# DACs.net
KiCad netlist of a schematic drawn in Altium Designer
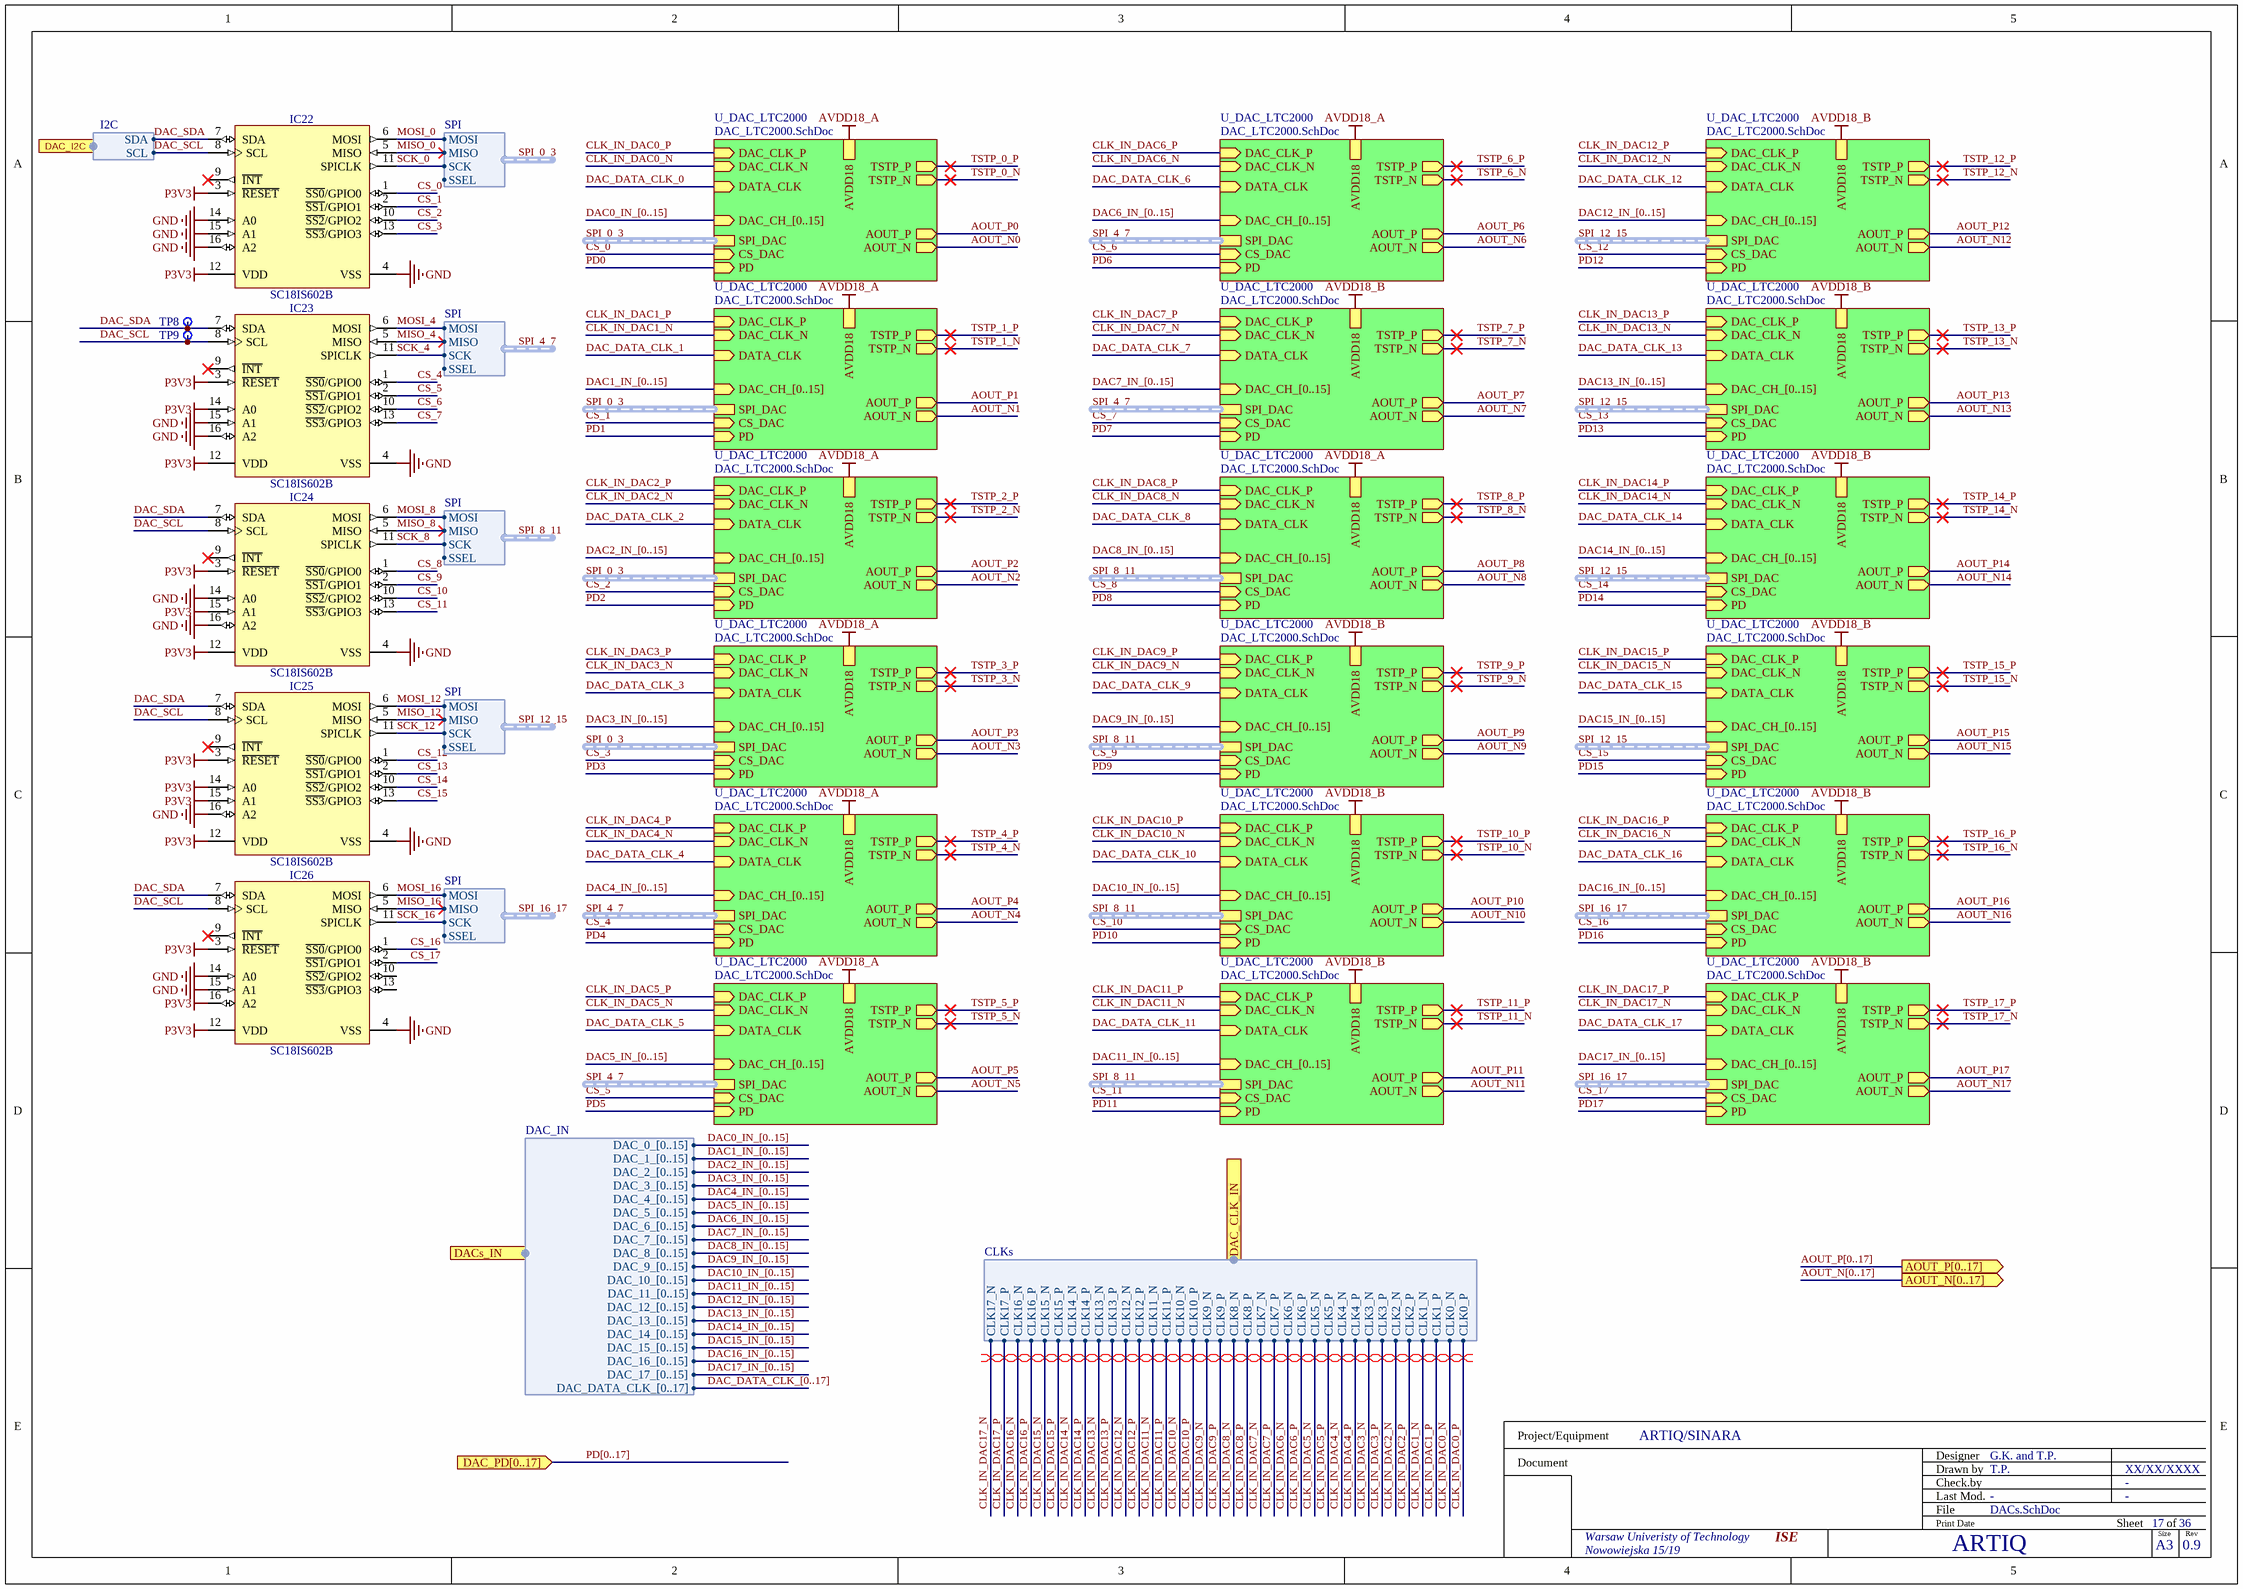
[diagram p0: DACs.SchDoc]

(export (version "E")
  (design (tool "Eeschema 10.0.6"))
  (components
    (comp (ref "IC22")
      (value "SC18IS602B")
      (footprint "SOP65P640X110-16N")
      (description "I2C-bus to SPI bridge")
      (fields (field (name "MANUFACTURER") "NXP SEMICONDUCTORS") (field (name "AUTHOR") "CERN DEM MR"))
      (libsource (lib "ICs And Semiconductors") (part "SC18IS602B"))
    )
    (comp (ref "IC23")
      (value "SC18IS602B")
      (footprint "SOP65P640X110-16N")
      (description "I2C-bus to SPI bridge")
      (fields (field (name "MANUFACTURER") "NXP SEMICONDUCTORS") (field (name "AUTHOR") "CERN DEM MR"))
      (libsource (lib "ICs And Semiconductors") (part "SC18IS602B"))
    )
    (comp (ref "IC24")
      (value "SC18IS602B")
      (footprint "SOP65P640X110-16N")
      (description "I2C-bus to SPI bridge")
      (fields (field (name "MANUFACTURER") "NXP SEMICONDUCTORS") (field (name "AUTHOR") "CERN DEM MR"))
      (libsource (lib "ICs And Semiconductors") (part "SC18IS602B"))
    )
    (comp (ref "IC25")
      (value "SC18IS602B")
      (footprint "SOP65P640X110-16N")
      (description "I2C-bus to SPI bridge")
      (fields (field (name "MANUFACTURER") "NXP SEMICONDUCTORS") (field (name "AUTHOR") "CERN DEM MR"))
      (libsource (lib "ICs And Semiconductors") (part "SC18IS602B"))
    )
    (comp (ref "IC26")
      (value "SC18IS602B")
      (footprint "SOP65P640X110-16N")
      (description "I2C-bus to SPI bridge")
      (fields (field (name "MANUFACTURER") "NXP SEMICONDUCTORS") (field (name "AUTHOR") "CERN DEM MR"))
      (libsource (lib "ICs And Semiconductors") (part "SC18IS602B"))
    )
    (comp (ref "TP8")
      (value "Test Point")
      (footprint "TPS127")
      (fields (field (name "PART NUMBER") "SMD_PAD_1.27X1.27MM") (field (name "AUTHOR") "CERN DEM JLC"))
      (libsource (lib "Eletro-mechanical") (part "Test Point"))
    )
    (comp (ref "TP9")
      (value "Test Point")
      (footprint "TPS127")
      (fields (field (name "PART NUMBER") "SMD_PAD_1.27X1.27MM") (field (name "AUTHOR") "CERN DEM JLC"))
      (libsource (lib "Eletro-mechanical") (part "Test Point"))
    )
  )
  (nets
    (net (code "376") (name "/CS_0") (class "Default")
      (node (ref "IC22") (pin "1") (pinfunction "~{SS0}/GPIO0_1") (pintype "bidirectional"))
    )
    (net (code "377") (name "/CS_1") (class "Default")
      (node (ref "IC22") (pin "2") (pinfunction "~{SS1}/GPIO1_2") (pintype "bidirectional"))
    )
    (net (code "378") (name "/CS_2") (class "Default")
      (node (ref "IC22") (pin "10") (pinfunction "~{SS2}/GPIO2_10") (pintype "bidirectional"))
    )
    (net (code "379") (name "/CS_3") (class "Default")
      (node (ref "IC22") (pin "13") (pinfunction "~{SS3}/GPIO3_13") (pintype "bidirectional"))
    )
    (net (code "380") (name "/CS_4") (class "Default")
      (node (ref "IC23") (pin "1") (pinfunction "~{SS0}/GPIO0_1") (pintype "bidirectional"))
    )
    (net (code "381") (name "/CS_5") (class "Default")
      (node (ref "IC23") (pin "2") (pinfunction "~{SS1}/GPIO1_2") (pintype "bidirectional"))
    )
    (net (code "382") (name "/CS_6") (class "Default")
      (node (ref "IC23") (pin "10") (pinfunction "~{SS2}/GPIO2_10") (pintype "bidirectional"))
    )
    (net (code "383") (name "/CS_7") (class "Default")
      (node (ref "IC23") (pin "13") (pinfunction "~{SS3}/GPIO3_13") (pintype "bidirectional"))
    )
    (net (code "384") (name "/CS_8") (class "Default")
      (node (ref "IC24") (pin "1") (pinfunction "~{SS0}/GPIO0_1") (pintype "bidirectional"))
    )
    (net (code "385") (name "/CS_9") (class "Default")
      (node (ref "IC24") (pin "2") (pinfunction "~{SS1}/GPIO1_2") (pintype "bidirectional"))
    )
    (net (code "386") (name "/CS_10") (class "Default")
      (node (ref "IC24") (pin "10") (pinfunction "~{SS2}/GPIO2_10") (pintype "bidirectional"))
    )
    (net (code "387") (name "/CS_11") (class "Default")
      (node (ref "IC24") (pin "13") (pinfunction "~{SS3}/GPIO3_13") (pintype "bidirectional"))
    )
    (net (code "388") (name "/CS_12") (class "Default")
      (node (ref "IC25") (pin "1") (pinfunction "~{SS0}/GPIO0_1") (pintype "bidirectional"))
    )
    (net (code "389") (name "/CS_13") (class "Default")
      (node (ref "IC25") (pin "2") (pinfunction "~{SS1}/GPIO1_2") (pintype "bidirectional"))
    )
    (net (code "390") (name "/CS_14") (class "Default")
      (node (ref "IC25") (pin "10") (pinfunction "~{SS2}/GPIO2_10") (pintype "bidirectional"))
    )
    (net (code "391") (name "/CS_15") (class "Default")
      (node (ref "IC25") (pin "13") (pinfunction "~{SS3}/GPIO3_13") (pintype "bidirectional"))
    )
    (net (code "392") (name "/CS_16") (class "Default")
      (node (ref "IC26") (pin "1") (pinfunction "~{SS0}/GPIO0_1") (pintype "bidirectional"))
    )
    (net (code "393") (name "/CS_17") (class "Default")
      (node (ref "IC26") (pin "2") (pinfunction "~{SS1}/GPIO1_2") (pintype "bidirectional"))
    )
    (net (code "430") (name "/DAC_SCL") (class "Default")
      (node (ref "IC22") (pin "8") (pinfunction "SCL_8") (pintype "input"))
      (node (ref "IC23") (pin "8") (pinfunction "SCL_8") (pintype "input"))
      (node (ref "IC24") (pin "8") (pinfunction "SCL_8") (pintype "input"))
      (node (ref "IC25") (pin "8") (pinfunction "SCL_8") (pintype "input"))
      (node (ref "IC26") (pin "8") (pinfunction "SCL_8") (pintype "input"))
      (node (ref "TP9") (pin "1") (pinfunction "1_1") (pintype "bidirectional"))
    )
    (net (code "431") (name "/DAC_SDA") (class "Default")
      (node (ref "IC22") (pin "7") (pinfunction "SDA_7") (pintype "bidirectional"))
      (node (ref "IC23") (pin "7") (pinfunction "SDA_7") (pintype "bidirectional"))
      (node (ref "IC24") (pin "7") (pinfunction "SDA_7") (pintype "bidirectional"))
      (node (ref "IC25") (pin "7") (pinfunction "SDA_7") (pintype "bidirectional"))
      (node (ref "IC26") (pin "7") (pinfunction "SDA_7") (pintype "bidirectional"))
      (node (ref "TP8") (pin "1") (pinfunction "1_1") (pintype "bidirectional"))
    )
    (net (code "433") (name "/MISO_0") (class "Default")
      (node (ref "IC22") (pin "5") (pinfunction "MISO_5") (pintype "input+no_connect"))
    )
    (net (code "434") (name "/MISO_4") (class "Default")
      (node (ref "IC23") (pin "5") (pinfunction "MISO_5") (pintype "input+no_connect"))
    )
    (net (code "435") (name "/MISO_8") (class "Default")
      (node (ref "IC24") (pin "5") (pinfunction "MISO_5") (pintype "input+no_connect"))
    )
    (net (code "436") (name "/MISO_12") (class "Default")
      (node (ref "IC25") (pin "5") (pinfunction "MISO_5") (pintype "input+no_connect"))
    )
    (net (code "437") (name "/MISO_16") (class "Default")
      (node (ref "IC26") (pin "5") (pinfunction "MISO_5") (pintype "input+no_connect"))
    )
    (net (code "438") (name "/MOSI_0") (class "Default")
      (node (ref "IC22") (pin "6") (pinfunction "MOSI_6") (pintype "output"))
    )
    (net (code "439") (name "/MOSI_4") (class "Default")
      (node (ref "IC23") (pin "6") (pinfunction "MOSI_6") (pintype "output"))
    )
    (net (code "440") (name "/MOSI_8") (class "Default")
      (node (ref "IC24") (pin "6") (pinfunction "MOSI_6") (pintype "output"))
    )
    (net (code "441") (name "/MOSI_12") (class "Default")
      (node (ref "IC25") (pin "6") (pinfunction "MOSI_6") (pintype "output"))
    )
    (net (code "442") (name "/MOSI_16") (class "Default")
      (node (ref "IC26") (pin "6") (pinfunction "MOSI_6") (pintype "output"))
    )
    (net (code "462") (name "/SCK_0") (class "Default")
      (node (ref "IC22") (pin "11") (pinfunction "SPICLK_11") (pintype "output"))
    )
    (net (code "463") (name "/SCK_4") (class "Default")
      (node (ref "IC23") (pin "11") (pinfunction "SPICLK_11") (pintype "output"))
    )
    (net (code "464") (name "/SCK_8") (class "Default")
      (node (ref "IC24") (pin "11") (pinfunction "SPICLK_11") (pintype "output"))
    )
    (net (code "465") (name "/SCK_12") (class "Default")
      (node (ref "IC25") (pin "11") (pinfunction "SPICLK_11") (pintype "output"))
    )
    (net (code "466") (name "/SCK_16") (class "Default")
      (node (ref "IC26") (pin "11") (pinfunction "SPICLK_11") (pintype "output"))
    )
    (net (code "517") (name "GND") (class "Default")
      (node (ref "IC22") (pin "14") (pinfunction "A0_14") (pintype "input"))
      (node (ref "IC22") (pin "15") (pinfunction "A1_15") (pintype "input"))
      (node (ref "IC22") (pin "16") (pinfunction "A2_16") (pintype "bidirectional"))
      (node (ref "IC22") (pin "4") (pinfunction "VSS_4") (pintype "power_in"))
      (node (ref "IC23") (pin "15") (pinfunction "A1_15") (pintype "input"))
      (node (ref "IC23") (pin "16") (pinfunction "A2_16") (pintype "bidirectional"))
      (node (ref "IC23") (pin "4") (pinfunction "VSS_4") (pintype "power_in"))
      (node (ref "IC24") (pin "14") (pinfunction "A0_14") (pintype "input"))
      (node (ref "IC24") (pin "16") (pinfunction "A2_16") (pintype "bidirectional"))
      (node (ref "IC24") (pin "4") (pinfunction "VSS_4") (pintype "power_in"))
      (node (ref "IC25") (pin "16") (pinfunction "A2_16") (pintype "bidirectional"))
      (node (ref "IC25") (pin "4") (pinfunction "VSS_4") (pintype "power_in"))
      (node (ref "IC26") (pin "14") (pinfunction "A0_14") (pintype "input"))
      (node (ref "IC26") (pin "15") (pinfunction "A1_15") (pintype "input"))
      (node (ref "IC26") (pin "4") (pinfunction "VSS_4") (pintype "power_in"))
    )
    (net (code "518") (name "P3V3") (class "Default")
      (node (ref "IC22") (pin "12") (pinfunction "VDD_12") (pintype "power_in"))
      (node (ref "IC22") (pin "3") (pinfunction "~{RESET}_3") (pintype "input"))
      (node (ref "IC23") (pin "12") (pinfunction "VDD_12") (pintype "power_in"))
      (node (ref "IC23") (pin "14") (pinfunction "A0_14") (pintype "input"))
      (node (ref "IC23") (pin "3") (pinfunction "~{RESET}_3") (pintype "input"))
      (node (ref "IC24") (pin "12") (pinfunction "VDD_12") (pintype "power_in"))
      (node (ref "IC24") (pin "15") (pinfunction "A1_15") (pintype "input"))
      (node (ref "IC24") (pin "3") (pinfunction "~{RESET}_3") (pintype "input"))
      (node (ref "IC25") (pin "12") (pinfunction "VDD_12") (pintype "power_in"))
      (node (ref "IC25") (pin "14") (pinfunction "A0_14") (pintype "input"))
      (node (ref "IC25") (pin "15") (pinfunction "A1_15") (pintype "input"))
      (node (ref "IC25") (pin "3") (pinfunction "~{RESET}_3") (pintype "input"))
      (node (ref "IC26") (pin "12") (pinfunction "VDD_12") (pintype "power_in"))
      (node (ref "IC26") (pin "16") (pinfunction "A2_16") (pintype "bidirectional"))
      (node (ref "IC26") (pin "3") (pinfunction "~{RESET}_3") (pintype "input"))
    )
    (net (code "519") (name "unconnected-(IC22-~{INT}-Pad9)") (class "Default")
      (node (ref "IC22") (pin "9") (pinfunction "~{INT}_9") (pintype "output+no_connect"))
    )
    (net (code "520") (name "unconnected-(IC23-~{INT}-Pad9)") (class "Default")
      (node (ref "IC23") (pin "9") (pinfunction "~{INT}_9") (pintype "output+no_connect"))
    )
    (net (code "521") (name "unconnected-(IC24-~{INT}-Pad9)") (class "Default")
      (node (ref "IC24") (pin "9") (pinfunction "~{INT}_9") (pintype "output+no_connect"))
    )
    (net (code "522") (name "unconnected-(IC25-~{INT}-Pad9)") (class "Default")
      (node (ref "IC25") (pin "9") (pinfunction "~{INT}_9") (pintype "output+no_connect"))
    )
    (net (code "523") (name "unconnected-(IC26-~{INT}-Pad9)") (class "Default")
      (node (ref "IC26") (pin "9") (pinfunction "~{INT}_9") (pintype "output+no_connect"))
    )
    (net (code "524") (name "unconnected-(IC26-~{SS2}{slash}GPIO2-Pad10)") (class "Default")
      (node (ref "IC26") (pin "10") (pinfunction "~{SS2}/GPIO2_10") (pintype "bidirectional"))
    )
    (net (code "525") (name "unconnected-(IC26-~{SS3}{slash}GPIO3-Pad13)") (class "Default")
      (node (ref "IC26") (pin "13") (pinfunction "~{SS3}/GPIO3_13") (pintype "bidirectional"))
    )
  )
)
